# schematic_r3.net
KiCad netlist of a schematic drawn in EAGLE
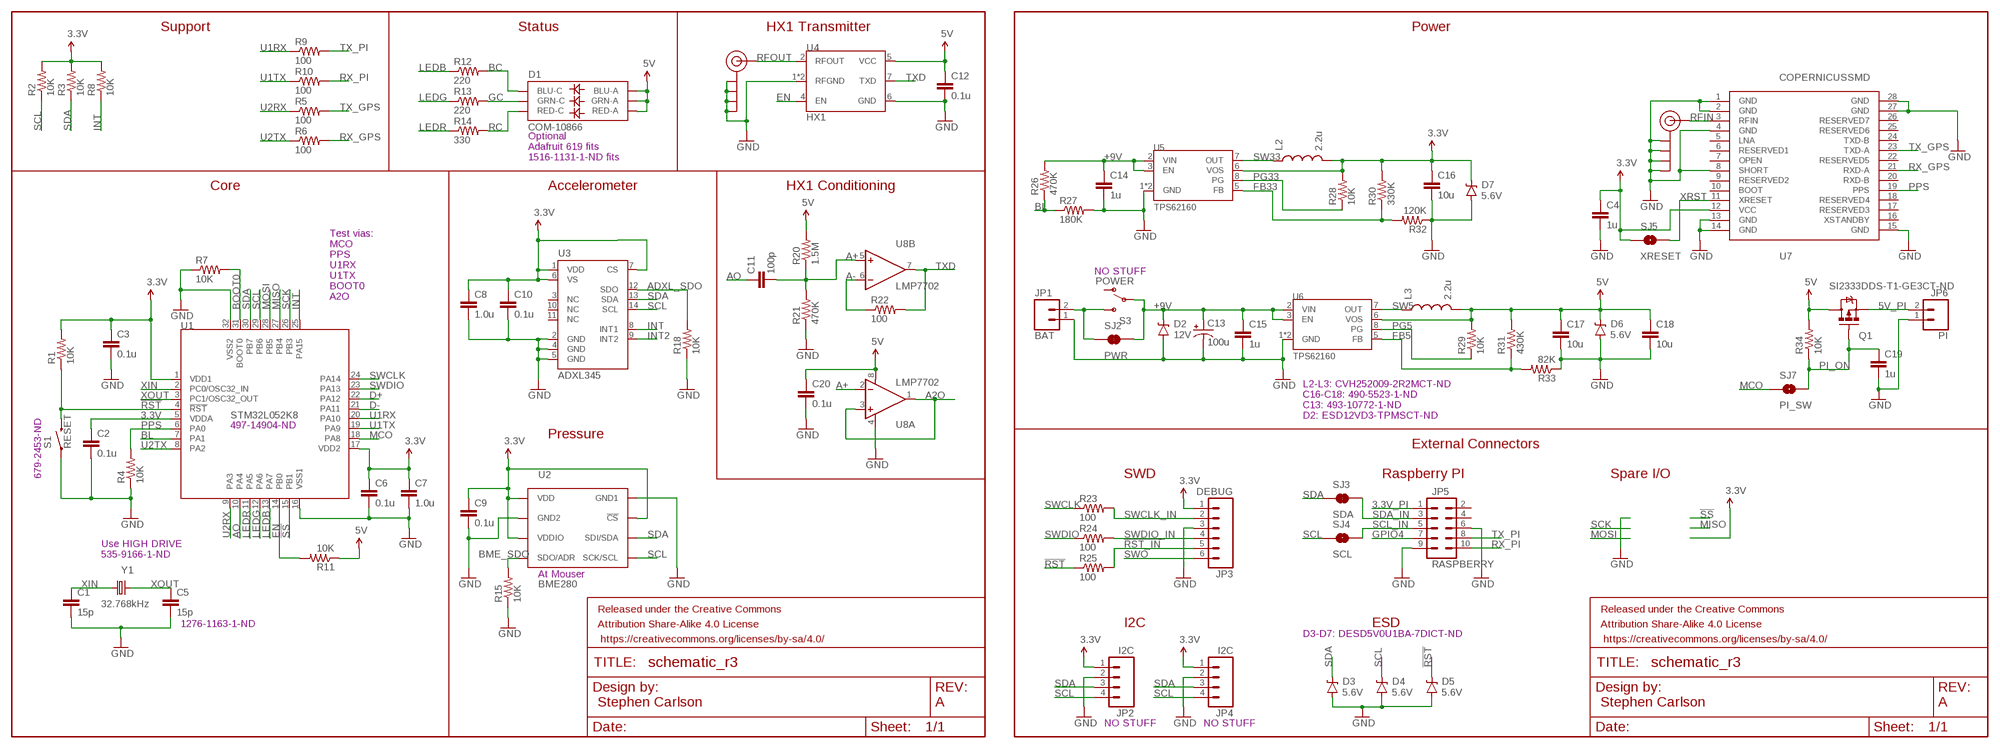
[diagram p0: schematic, sheet 1]

(export (version "E")
  (design (tool "Eeschema 10.0.6"))
  (components
    (comp (ref "C1")
      (value "15p")
      (footprint "eagle-import:0805")
      (libsource (lib "eagle-import") (part "CAP0805"))
    )
    (comp (ref "C2")
      (value "0.1u")
      (footprint "eagle-import:0805")
      (libsource (lib "eagle-import") (part "CAP0805"))
    )
    (comp (ref "C3")
      (value "0.1u")
      (footprint "eagle-import:0805")
      (libsource (lib "eagle-import") (part "CAP0805"))
    )
    (comp (ref "C4")
      (value "1u")
      (footprint "eagle-import:0805")
      (libsource (lib "eagle-import") (part "CAP0805"))
    )
    (comp (ref "C5")
      (value "15p")
      (footprint "eagle-import:0805")
      (libsource (lib "eagle-import") (part "CAP0805"))
    )
    (comp (ref "C6")
      (value "0.1u")
      (footprint "eagle-import:0805")
      (libsource (lib "eagle-import") (part "CAP0805"))
    )
    (comp (ref "C7")
      (value "1.0u")
      (footprint "eagle-import:0805")
      (libsource (lib "eagle-import") (part "CAP0805"))
    )
    (comp (ref "C8")
      (value "1.0u")
      (footprint "eagle-import:0805")
      (libsource (lib "eagle-import") (part "CAP0805"))
    )
    (comp (ref "C9")
      (value "0.1u")
      (footprint "eagle-import:0805")
      (libsource (lib "eagle-import") (part "CAP0805"))
    )
    (comp (ref "C10")
      (value "0.1u")
      (footprint "eagle-import:0805")
      (libsource (lib "eagle-import") (part "CAP0805"))
    )
    (comp (ref "C11")
      (value "100p")
      (footprint "eagle-import:0805")
      (libsource (lib "eagle-import") (part "CAP0805"))
    )
    (comp (ref "C12")
      (value "0.1u")
      (footprint "eagle-import:0805")
      (libsource (lib "eagle-import") (part "CAP0805"))
    )
    (comp (ref "C13")
      (value "100u")
      (footprint "eagle-import:CPOL-RADIAL-10UF-25V")
      (libsource (lib "eagle-import") (part "CAP_POLPTH2"))
    )
    (comp (ref "C14")
      (value "1u")
      (footprint "eagle-import:0805")
      (libsource (lib "eagle-import") (part "CAP0805"))
    )
    (comp (ref "C15")
      (value "1u")
      (footprint "eagle-import:0805")
      (libsource (lib "eagle-import") (part "CAP0805"))
    )
    (comp (ref "C16")
      (value "10u")
      (footprint "eagle-import:0805")
      (libsource (lib "eagle-import") (part "CAP0805"))
    )
    (comp (ref "C17")
      (value "10u")
      (footprint "eagle-import:0805")
      (libsource (lib "eagle-import") (part "CAP0805"))
    )
    (comp (ref "C18")
      (value "10u")
      (footprint "eagle-import:0805")
      (libsource (lib "eagle-import") (part "CAP0805"))
    )
    (comp (ref "C19")
      (value "1u")
      (footprint "eagle-import:0805")
      (libsource (lib "eagle-import") (part "CAP0805"))
    )
    (comp (ref "C20")
      (value "0.1u")
      (footprint "eagle-import:0805")
      (libsource (lib "eagle-import") (part "CAP0805"))
    )
    (comp (ref "D1")
      (value "COM-10866")
      (footprint "eagle-import:LED-TRICOLOR-5050")
      (libsource (lib "eagle-import") (part "LED-TRICOLOR-5050NO_IC"))
    )
    (comp (ref "D2")
      (value "12V")
      (footprint "eagle-import:SOD-323")
      (libsource (lib "eagle-import") (part "DIODE-ZENER5.6V"))
    )
    (comp (ref "D3")
      (value "5.6V")
      (footprint "eagle-import:SOD-323")
      (libsource (lib "eagle-import") (part "DIODE-ZENER5.6V"))
    )
    (comp (ref "D4")
      (value "5.6V")
      (footprint "eagle-import:SOD-323")
      (libsource (lib "eagle-import") (part "DIODE-ZENER5.6V"))
    )
    (comp (ref "D5")
      (value "5.6V")
      (footprint "eagle-import:SOD-323")
      (libsource (lib "eagle-import") (part "DIODE-ZENER5.6V"))
    )
    (comp (ref "D6")
      (value "5.6V")
      (footprint "eagle-import:SOD-323")
      (libsource (lib "eagle-import") (part "DIODE-ZENER5.6V"))
    )
    (comp (ref "D7")
      (value "5.6V")
      (footprint "eagle-import:SOD-323")
      (libsource (lib "eagle-import") (part "DIODE-ZENER5.6V"))
    )
    (comp (ref "FRAME1")
      (value "FRAME-LETTERNO_PACKAGE")
      (footprint "eagle-import:DUMMY")
      (fields (field (name "DESIGNER") "Nobody"))
      (libsource (lib "eagle-import") (part "FRAME-LETTERNO_PACKAGE"))
    )
    (comp (ref "FRAME2")
      (value "FRAME-LETTERNO_PACKAGE")
      (footprint "eagle-import:DUMMY")
      (fields (field (name "DESIGNER") "Nobody"))
      (libsource (lib "eagle-import") (part "FRAME-LETTERNO_PACKAGE"))
    )
    (comp (ref "J$1")
      (value "SMA_EDGE")
      (footprint "eagle-import:SMA-EDGE")
      (libsource (lib "eagle-import") (part "SMA_EDGE"))
    )
    (comp (ref "J$2")
      (value "SMA_EDGE")
      (footprint "eagle-import:SMA-EDGE")
      (libsource (lib "eagle-import") (part "SMA_EDGE"))
    )
    (comp (ref "JP1")
      (value "BAT")
      (footprint "eagle-import:1X02")
      (libsource (lib "eagle-import") (part "M02PTH"))
    )
    (comp (ref "JP2")
      (value "I2C")
      (footprint "eagle-import:1X04_LOCK")
      (libsource (lib "eagle-import") (part "M04LOCK"))
    )
    (comp (ref "JP3")
      (value "DEBUG")
      (footprint "eagle-import:1X06_LOCK")
      (libsource (lib "eagle-import") (part "M06LOCK"))
    )
    (comp (ref "JP4")
      (value "I2C")
      (footprint "eagle-import:1X04_LOCK")
      (libsource (lib "eagle-import") (part "M04LOCK"))
    )
    (comp (ref "JP5")
      (value "RASPBERRY")
      (footprint "eagle-import:AVR_ICSP")
      (libsource (lib "eagle-import") (part "M05X2PTH"))
    )
    (comp (ref "JP6")
      (value "PI")
      (footprint "eagle-import:1X02")
      (libsource (lib "eagle-import") (part "M02PTH"))
    )
    (comp (ref "L2")
      (value "2.2u")
      (footprint "eagle-import:1008")
      (libsource (lib "eagle-import") (part "INDUCTOR1008"))
    )
    (comp (ref "L3")
      (value "2.2u")
      (footprint "eagle-import:1008")
      (libsource (lib "eagle-import") (part "INDUCTOR1008"))
    )
    (comp (ref "Q1")
      (value "SI2333DDS-T1-GE3CT-ND")
      (footprint "eagle-import:SOT23-3")
      (libsource (lib "eagle-import") (part "MOSFET-PCHANNELSMD"))
    )
    (comp (ref "R1")
      (value "10K")
      (footprint "eagle-import:0805")
      (libsource (lib "eagle-import") (part "RESISTOR0805-RES"))
    )
    (comp (ref "R2")
      (value "10K")
      (footprint "eagle-import:0805")
      (libsource (lib "eagle-import") (part "RESISTOR0805-RES"))
    )
    (comp (ref "R3")
      (value "10K")
      (footprint "eagle-import:0805")
      (libsource (lib "eagle-import") (part "RESISTOR0805-RES"))
    )
    (comp (ref "R4")
      (value "10K")
      (footprint "eagle-import:0805")
      (libsource (lib "eagle-import") (part "RESISTOR0805-RES"))
    )
    (comp (ref "R5")
      (value "100")
      (footprint "eagle-import:0805")
      (libsource (lib "eagle-import") (part "RESISTOR0805-RES"))
    )
    (comp (ref "R6")
      (value "100")
      (footprint "eagle-import:0805")
      (libsource (lib "eagle-import") (part "RESISTOR0805-RES"))
    )
    (comp (ref "R7")
      (value "10K")
      (footprint "eagle-import:0805")
      (libsource (lib "eagle-import") (part "RESISTOR0805-RES"))
    )
    (comp (ref "R8")
      (value "10K")
      (footprint "eagle-import:0805")
      (libsource (lib "eagle-import") (part "RESISTOR0805-RES"))
    )
    (comp (ref "R9")
      (value "100")
      (footprint "eagle-import:0805")
      (libsource (lib "eagle-import") (part "RESISTOR0805-RES"))
    )
    (comp (ref "R10")
      (value "100")
      (footprint "eagle-import:0805")
      (libsource (lib "eagle-import") (part "RESISTOR0805-RES"))
    )
    (comp (ref "R11")
      (value "10K")
      (footprint "eagle-import:0805")
      (libsource (lib "eagle-import") (part "RESISTOR0805-RES"))
    )
    (comp (ref "R12")
      (value "220")
      (footprint "eagle-import:0805")
      (libsource (lib "eagle-import") (part "RESISTOR0805-RES"))
    )
    (comp (ref "R13")
      (value "220")
      (footprint "eagle-import:0805")
      (libsource (lib "eagle-import") (part "RESISTOR0805-RES"))
    )
    (comp (ref "R14")
      (value "330")
      (footprint "eagle-import:0805")
      (libsource (lib "eagle-import") (part "RESISTOR0805-RES"))
    )
    (comp (ref "R15")
      (value "10K")
      (footprint "eagle-import:0805")
      (libsource (lib "eagle-import") (part "RESISTOR0805-RES"))
    )
    (comp (ref "R18")
      (value "10K")
      (footprint "eagle-import:0805")
      (libsource (lib "eagle-import") (part "RESISTOR0805-RES"))
    )
    (comp (ref "R20")
      (value "1.5M")
      (footprint "eagle-import:0805")
      (libsource (lib "eagle-import") (part "RESISTOR0805-RES"))
    )
    (comp (ref "R21")
      (value "470K")
      (footprint "eagle-import:0805")
      (libsource (lib "eagle-import") (part "RESISTOR0805-RES"))
    )
    (comp (ref "R22")
      (value "100")
      (footprint "eagle-import:0805")
      (libsource (lib "eagle-import") (part "RESISTOR0805-RES"))
    )
    (comp (ref "R23")
      (value "100")
      (footprint "eagle-import:0805")
      (libsource (lib "eagle-import") (part "RESISTOR0805-RES"))
    )
    (comp (ref "R24")
      (value "100")
      (footprint "eagle-import:0805")
      (libsource (lib "eagle-import") (part "RESISTOR0805-RES"))
    )
    (comp (ref "R25")
      (value "100")
      (footprint "eagle-import:0805")
      (libsource (lib "eagle-import") (part "RESISTOR0805-RES"))
    )
    (comp (ref "R26")
      (value "470K")
      (footprint "eagle-import:0805")
      (libsource (lib "eagle-import") (part "RESISTOR0805-RES"))
    )
    (comp (ref "R27")
      (value "180K")
      (footprint "eagle-import:0805")
      (libsource (lib "eagle-import") (part "RESISTOR0805-RES"))
    )
    (comp (ref "R28")
      (value "10K")
      (footprint "eagle-import:0805")
      (libsource (lib "eagle-import") (part "RESISTOR0805-RES"))
    )
    (comp (ref "R29")
      (value "10K")
      (footprint "eagle-import:0805")
      (libsource (lib "eagle-import") (part "RESISTOR0805-RES"))
    )
    (comp (ref "R30")
      (value "330K")
      (footprint "eagle-import:0805")
      (libsource (lib "eagle-import") (part "RESISTOR0805-RES"))
    )
    (comp (ref "R31")
      (value "430K")
      (footprint "eagle-import:0805")
      (libsource (lib "eagle-import") (part "RESISTOR0805-RES"))
    )
    (comp (ref "R32")
      (value "120K")
      (footprint "eagle-import:0805")
      (libsource (lib "eagle-import") (part "RESISTOR0805-RES"))
    )
    (comp (ref "R33")
      (value "82K")
      (footprint "eagle-import:0805")
      (libsource (lib "eagle-import") (part "RESISTOR0805-RES"))
    )
    (comp (ref "R34")
      (value "10K")
      (footprint "eagle-import:0805")
      (libsource (lib "eagle-import") (part "RESISTOR0805-RES"))
    )
    (comp (ref "S1")
      (value "RESET")
      (footprint "eagle-import:TACTILE-PTH-THIN")
      (libsource (lib "eagle-import") (part "SWITCH"))
    )
    (comp (ref "S3")
      (value "POWER")
      (footprint "eagle-import:SWITCH-SPDT")
      (libsource (lib "eagle-import") (part "SWITCH-SPDTPTH"))
    )
    (comp (ref "SJ2")
      (value "PWR")
      (footprint "eagle-import:PAD-JUMPER-2-NC_BY_TRACE_YES_SILK")
      (libsource (lib "eagle-import") (part "JUMPER-PAD-2-NC_BY_TRACE"))
    )
    (comp (ref "SJ3")
      (value "SDA")
      (footprint "eagle-import:PAD-JUMPER-2-NC_BY_TRACE_YES_SILK")
      (libsource (lib "eagle-import") (part "JUMPER-PAD-2-NC_BY_TRACE"))
    )
    (comp (ref "SJ4")
      (value "SCL")
      (footprint "eagle-import:PAD-JUMPER-2-NC_BY_TRACE_YES_SILK")
      (libsource (lib "eagle-import") (part "JUMPER-PAD-2-NC_BY_TRACE"))
    )
    (comp (ref "SJ5")
      (value "XRESET")
      (footprint "eagle-import:PAD-JUMPER-2-NO_YES_SILK")
      (libsource (lib "eagle-import") (part "JUMPER-PAD-2-NOYES_SILK"))
    )
    (comp (ref "SJ7")
      (value "PI_SW")
      (footprint "eagle-import:PAD-JUMPER-2-NO_YES_SILK")
      (libsource (lib "eagle-import") (part "JUMPER-PAD-2-NOYES_SILK"))
    )
    (comp (ref "U1")
      (value "STM32L052K8")
      (footprint "eagle-import:TQFP32-08")
      (libsource (lib "eagle-import") (part "STM32L05K"))
    )
    (comp (ref "U2")
      (value "BME280")
      (footprint "eagle-import:BME280_LGA")
      (libsource (lib "eagle-import") (part "BME280"))
    )
    (comp (ref "U3")
      (value "ADXL345")
      (footprint "eagle-import:LGA14")
      (libsource (lib "eagle-import") (part "ADXL345"))
    )
    (comp (ref "U4")
      (value "HX1")
      (footprint "eagle-import:1X12")
      (libsource (lib "eagle-import") (part "HX1"))
    )
    (comp (ref "U5")
      (value "TPS62160")
      (footprint "eagle-import:MSOP8")
      (libsource (lib "eagle-import") (part "TPS62160"))
    )
    (comp (ref "U6")
      (value "TPS62160")
      (footprint "eagle-import:MSOP8")
      (libsource (lib "eagle-import") (part "TPS62160"))
    )
    (comp (ref "U7")
      (value "COPERNICUSSMD")
      (footprint "eagle-import:COPERNICUS")
      (libsource (lib "eagle-import") (part "COPERNICUSSMD"))
    )
    (comp (ref "U8")
      (value "LMP7702")
      (footprint "eagle-import:SO08")
      (libsource (lib "eagle-import") (part "OPAMP-DUALU"))
    )
    (comp (ref "Y1")
      (value "32.768kHz")
      (footprint "eagle-import:ABS25")
      (libsource (lib "eagle-import") (part "CRYSTAL"))
    )
  )
  (nets
    (net (code "1") (name "/+9V") (class "Default")
      (node (ref "C13") (pin "1") (pinfunction "+_1") (pintype "passive"))
      (node (ref "C14") (pin "1") (pinfunction "1_1") (pintype "passive"))
      (node (ref "C15") (pin "1") (pinfunction "1_1") (pintype "passive"))
      (node (ref "D2") (pin "C") (pinfunction "C_C") (pintype "passive"))
      (node (ref "R26") (pin "2") (pinfunction "2_2") (pintype "passive"))
      (node (ref "S3") (pin "2") (pinfunction "P_2") (pintype "passive"))
      (node (ref "SJ2") (pin "2") (pinfunction "2_2") (pintype "passive"))
      (node (ref "U5") (pin "2") (pinfunction "VIN_2") (pintype "power_in"))
      (node (ref "U5") (pin "3") (pinfunction "EN_3") (pintype "input"))
      (node (ref "U6") (pin "2") (pinfunction "VIN_2") (pintype "power_in"))
      (node (ref "U6") (pin "3") (pinfunction "EN_3") (pintype "input"))
    )
    (net (code "2") (name "/3.3V_PI") (class "Default")
      (node (ref "JP5") (pin "1") (pinfunction "1_1") (pintype "passive"))
    )
    (net (code "3") (name "/5V_PI") (class "Default")
      (node (ref "JP6") (pin "2") (pinfunction "2_2") (pintype "passive"))
      (node (ref "Q1") (pin "2") (pinfunction "S_2") (pintype "passive"))
    )
    (net (code "4") (name "/A+") (class "Default")
      (node (ref "C11") (pin "2") (pinfunction "2_2") (pintype "passive"))
      (node (ref "R20") (pin "1") (pinfunction "1_1") (pintype "passive"))
      (node (ref "R21") (pin "2") (pinfunction "2_2") (pintype "passive"))
      (node (ref "U8") (pin "2") (pinfunction "-IN_2") (pintype "input"))
      (node (ref "U8") (pin "5") (pinfunction "+IN_5") (pintype "input"))
    )
    (net (code "5") (name "/A-") (class "Default")
      (node (ref "R22") (pin "1") (pinfunction "1_1") (pintype "passive"))
      (node (ref "U8") (pin "6") (pinfunction "-IN_6") (pintype "input"))
    )
    (net (code "6") (name "/A2O") (class "Default")
      (node (ref "U8") (pin "1") (pinfunction "OUT_1") (pintype "output"))
      (node (ref "U8") (pin "3") (pinfunction "+IN_3") (pintype "input"))
    )
    (net (code "7") (name "/ADXL_SDO") (class "Default")
      (node (ref "R18") (pin "2") (pinfunction "2_2") (pintype "passive"))
      (node (ref "U3") (pin "12") (pinfunction "SDO_12") (pintype "bidirectional"))
    )
    (net (code "8") (name "/AO") (class "Default")
      (node (ref "C11") (pin "1") (pinfunction "1_1") (pintype "passive"))
      (node (ref "U1") (pin "10") (pinfunction "PA4_10") (pintype "bidirectional"))
    )
    (net (code "9") (name "/BC") (class "Default")
      (node (ref "D1") (pin "4") (pinfunction "BLU-C_4") (pintype "bidirectional"))
      (node (ref "R12") (pin "2") (pinfunction "2_2") (pintype "passive"))
    )
    (net (code "10") (name "/BL") (class "Default")
      (node (ref "R26") (pin "1") (pinfunction "1_1") (pintype "passive"))
      (node (ref "R27") (pin "1") (pinfunction "1_1") (pintype "passive"))
      (node (ref "U1") (pin "7") (pinfunction "PA1_7") (pintype "bidirectional"))
    )
    (net (code "11") (name "/BME_SDO") (class "Default")
      (node (ref "R15") (pin "2") (pinfunction "2_2") (pintype "passive"))
      (node (ref "U2") (pin "P$5") (pinfunction "SDO/ADR_P$5") (pintype "bidirectional"))
    )
    (net (code "12") (name "/BOOT0") (class "Default")
      (node (ref "R7") (pin "2") (pinfunction "2_2") (pintype "passive"))
      (node (ref "U1") (pin "31") (pinfunction "BOOT0_31") (pintype "input"))
    )
    (net (code "13") (name "/D+") (class "Default")
      (node (ref "U1") (pin "22") (pinfunction "PA12_22") (pintype "bidirectional"))
    )
    (net (code "14") (name "/D-") (class "Default")
      (node (ref "U1") (pin "21") (pinfunction "PA11_21") (pintype "bidirectional"))
    )
    (net (code "15") (name "/EN") (class "Default")
      (node (ref "R11") (pin "2") (pinfunction "2_2") (pintype "passive"))
      (node (ref "U1") (pin "14") (pinfunction "PB0_14") (pintype "bidirectional"))
      (node (ref "U4") (pin "4") (pinfunction "EN_4") (pintype "input"))
    )
    (net (code "16") (name "/FB5") (class "Default")
      (node (ref "R31") (pin "1") (pinfunction "1_1") (pintype "passive"))
      (node (ref "R33") (pin "2") (pinfunction "2_2") (pintype "passive"))
      (node (ref "U6") (pin "5") (pinfunction "FB_5") (pintype "input"))
    )
    (net (code "17") (name "/FB33") (class "Default")
      (node (ref "R30") (pin "1") (pinfunction "1_1") (pintype "passive"))
      (node (ref "R32") (pin "2") (pinfunction "2_2") (pintype "passive"))
      (node (ref "U5") (pin "5") (pinfunction "FB_5") (pintype "input"))
    )
    (net (code "18") (name "/GC") (class "Default")
      (node (ref "D1") (pin "6") (pinfunction "GRN-C_6") (pintype "bidirectional"))
      (node (ref "R13") (pin "2") (pinfunction "2_2") (pintype "passive"))
    )
    (net (code "19") (name "/GPIO4") (class "Default")
      (node (ref "JP5") (pin "7") (pinfunction "7_7") (pintype "passive"))
    )
    (net (code "20") (name "/INT") (class "Default")
      (node (ref "R8") (pin "1") (pinfunction "1_1") (pintype "passive"))
      (node (ref "U1") (pin "25") (pinfunction "PA15_25") (pintype "bidirectional"))
      (node (ref "U3") (pin "8") (pinfunction "INT1_8") (pintype "bidirectional"))
    )
    (net (code "21") (name "/INT2") (class "Default")
      (node (ref "U3") (pin "9") (pinfunction "INT2_9") (pintype "bidirectional"))
    )
    (net (code "22") (name "/LEDB") (class "Default")
      (node (ref "R12") (pin "1") (pinfunction "1_1") (pintype "passive"))
      (node (ref "U1") (pin "13") (pinfunction "PA7_13") (pintype "bidirectional"))
    )
    (net (code "23") (name "/LEDG") (class "Default")
      (node (ref "R13") (pin "1") (pinfunction "1_1") (pintype "passive"))
      (node (ref "U1") (pin "12") (pinfunction "PA6_12") (pintype "bidirectional"))
    )
    (net (code "24") (name "/LEDR") (class "Default")
      (node (ref "R14") (pin "1") (pinfunction "1_1") (pintype "passive"))
      (node (ref "U1") (pin "11") (pinfunction "PA5_11") (pintype "bidirectional"))
    )
    (net (code "25") (name "/MCO") (class "Default")
      (node (ref "SJ7") (pin "1") (pinfunction "1_1") (pintype "passive"))
      (node (ref "U1") (pin "18") (pinfunction "PA8_18") (pintype "bidirectional"))
    )
    (net (code "26") (name "/MISO") (class "Default")
      (node (ref "U1") (pin "27") (pinfunction "PB4_27") (pintype "bidirectional"))
    )
    (net (code "27") (name "/MOSI") (class "Default")
      (node (ref "U1") (pin "28") (pinfunction "PB5_28") (pintype "bidirectional"))
    )
    (net (code "28") (name "/PG5") (class "Default")
      (node (ref "R29") (pin "1") (pinfunction "1_1") (pintype "passive"))
      (node (ref "U6") (pin "8") (pinfunction "PG_8") (pintype "open_collector"))
    )
    (net (code "29") (name "/PG33") (class "Default")
      (node (ref "R28") (pin "1") (pinfunction "1_1") (pintype "passive"))
      (node (ref "U5") (pin "8") (pinfunction "PG_8") (pintype "open_collector"))
    )
    (net (code "30") (name "/PI_ON") (class "Default")
      (node (ref "C19") (pin "1") (pinfunction "1_1") (pintype "passive"))
      (node (ref "Q1") (pin "1") (pinfunction "G_1") (pintype "passive"))
      (node (ref "R34") (pin "1") (pinfunction "1_1") (pintype "passive"))
      (node (ref "SJ7") (pin "2") (pinfunction "2_2") (pintype "passive"))
    )
    (net (code "31") (name "/PPS") (class "Default")
      (node (ref "R4") (pin "2") (pinfunction "2_2") (pintype "passive"))
      (node (ref "U1") (pin "6") (pinfunction "PA0_6") (pintype "bidirectional"))
      (node (ref "U7") (pin "19") (pinfunction "PPS_19") (pintype "bidirectional"))
    )
    (net (code "32") (name "/RC") (class "Default")
      (node (ref "D1") (pin "5") (pinfunction "RED-C_5") (pintype "bidirectional"))
      (node (ref "R14") (pin "2") (pinfunction "2_2") (pintype "passive"))
    )
    (net (code "33") (name "/RFIN") (class "Default")
      (node (ref "J$2") (pin "SIG") (pinfunction "SIGNAL_SIG") (pintype "bidirectional"))
      (node (ref "U7") (pin "3") (pinfunction "RFIN_3") (pintype "bidirectional"))
    )
    (net (code "34") (name "/RFOUT") (class "Default")
      (node (ref "J$1") (pin "SIG") (pinfunction "SIGNAL_SIG") (pintype "bidirectional"))
      (node (ref "U4") (pin "2") (pinfunction "RFOUT_2") (pintype "output"))
    )
    (net (code "35") (name "/RX_GPS") (class "Default")
      (node (ref "R6") (pin "2") (pinfunction "2_2") (pintype "passive"))
      (node (ref "U7") (pin "21") (pinfunction "RXD-A_21") (pintype "bidirectional"))
    )
    (net (code "36") (name "/RX_PI") (class "Default")
      (node (ref "JP5") (pin "10") (pinfunction "10_10") (pintype "passive"))
      (node (ref "R10") (pin "2") (pinfunction "2_2") (pintype "passive"))
    )
    (net (code "37") (name "/SCK") (class "Default")
      (node (ref "U1") (pin "26") (pinfunction "PB3_26") (pintype "bidirectional"))
    )
    (net (code "38") (name "/SCL") (class "Default")
      (node (ref "D4") (pin "C") (pinfunction "C_C") (pintype "passive"))
      (node (ref "JP2") (pin "4") (pinfunction "4_4") (pintype "passive"))
      (node (ref "JP4") (pin "4") (pinfunction "4_4") (pintype "passive"))
      (node (ref "R2") (pin "1") (pinfunction "1_1") (pintype "passive"))
      (node (ref "SJ4") (pin "1") (pinfunction "1_1") (pintype "passive"))
      (node (ref "U1") (pin "29") (pinfunction "PB6_29") (pintype "bidirectional"))
      (node (ref "U2") (pin "P$4") (pinfunction "SCK/SCL_P$4") (pintype "bidirectional"))
      (node (ref "U3") (pin "14") (pinfunction "SCL_14") (pintype "bidirectional"))
    )
    (net (code "39") (name "/SCL_IN") (class "Default")
      (node (ref "JP5") (pin "5") (pinfunction "5_5") (pintype "passive"))
      (node (ref "SJ4") (pin "2") (pinfunction "2_2") (pintype "passive"))
    )
    (net (code "40") (name "/SDA") (class "Default")
      (node (ref "D3") (pin "C") (pinfunction "C_C") (pintype "passive"))
      (node (ref "JP2") (pin "3") (pinfunction "3_3") (pintype "passive"))
      (node (ref "JP4") (pin "3") (pinfunction "3_3") (pintype "passive"))
      (node (ref "R3") (pin "1") (pinfunction "1_1") (pintype "passive"))
      (node (ref "SJ3") (pin "1") (pinfunction "1_1") (pintype "passive"))
      (node (ref "U1") (pin "30") (pinfunction "PB7_30") (pintype "bidirectional"))
      (node (ref "U2") (pin "P$3") (pinfunction "SDI/SDA_P$3") (pintype "bidirectional"))
      (node (ref "U3") (pin "13") (pinfunction "SDA_13") (pintype "bidirectional"))
    )
    (net (code "41") (name "/SDA_IN") (class "Default")
      (node (ref "JP5") (pin "3") (pinfunction "3_3") (pintype "passive"))
      (node (ref "SJ3") (pin "2") (pinfunction "2_2") (pintype "passive"))
    )
    (net (code "42") (name "/SW5") (class "Default")
      (node (ref "L3") (pin "1") (pinfunction "1_1") (pintype "passive"))
      (node (ref "U6") (pin "7") (pinfunction "OUT_7") (pintype "output"))
    )
    (net (code "43") (name "/SW33") (class "Default")
      (node (ref "L2") (pin "1") (pinfunction "1_1") (pintype "passive"))
      (node (ref "U5") (pin "7") (pinfunction "OUT_7") (pintype "output"))
    )
    (net (code "44") (name "/SWCLK") (class "Default")
      (node (ref "R23") (pin "1") (pinfunction "1_1") (pintype "passive"))
      (node (ref "U1") (pin "24") (pinfunction "PA14_24") (pintype "bidirectional"))
    )
    (net (code "45") (name "/SWCLK_IN") (class "Default")
      (node (ref "JP3") (pin "2") (pinfunction "2_2") (pintype "passive"))
      (node (ref "R23") (pin "2") (pinfunction "2_2") (pintype "passive"))
    )
    (net (code "46") (name "/SWDIO") (class "Default")
      (node (ref "R24") (pin "1") (pinfunction "1_1") (pintype "passive"))
      (node (ref "U1") (pin "23") (pinfunction "PA13_23") (pintype "bidirectional"))
    )
    (net (code "47") (name "/SWDIO_IN") (class "Default")
      (node (ref "JP3") (pin "4") (pinfunction "4_4") (pintype "passive"))
      (node (ref "R24") (pin "2") (pinfunction "2_2") (pintype "passive"))
    )
    (net (code "48") (name "/SWO") (class "Default")
      (node (ref "JP3") (pin "6") (pinfunction "6_6") (pintype "passive"))
    )
    (net (code "49") (name "/TXD") (class "Default")
      (node (ref "R22") (pin "2") (pinfunction "2_2") (pintype "passive"))
      (node (ref "U4") (pin "7") (pinfunction "TXD_7") (pintype "input"))
      (node (ref "U8") (pin "7") (pinfunction "OUT_7") (pintype "output"))
    )
    (net (code "50") (name "/TX_GPS") (class "Default")
      (node (ref "R5") (pin "2") (pinfunction "2_2") (pintype "passive"))
      (node (ref "U7") (pin "23") (pinfunction "TXD-A_23") (pintype "bidirectional"))
    )
    (net (code "51") (name "/TX_PI") (class "Default")
      (node (ref "JP5") (pin "8") (pinfunction "8_8") (pintype "passive"))
      (node (ref "R9") (pin "2") (pinfunction "2_2") (pintype "passive"))
    )
    (net (code "52") (name "/U1RX") (class "Default")
      (node (ref "R9") (pin "1") (pinfunction "1_1") (pintype "passive"))
      (node (ref "U1") (pin "20") (pinfunction "PA10_20") (pintype "bidirectional"))
    )
    (net (code "53") (name "/U1TX") (class "Default")
      (node (ref "R10") (pin "1") (pinfunction "1_1") (pintype "passive"))
      (node (ref "U1") (pin "19") (pinfunction "PA9_19") (pintype "bidirectional"))
    )
    (net (code "54") (name "/U2RX") (class "Default")
      (node (ref "R5") (pin "1") (pinfunction "1_1") (pintype "passive"))
      (node (ref "U1") (pin "9") (pinfunction "PA3_9") (pintype "bidirectional"))
    )
    (net (code "55") (name "/U2TX") (class "Default")
      (node (ref "R6") (pin "1") (pinfunction "1_1") (pintype "passive"))
      (node (ref "U1") (pin "8") (pinfunction "PA2_8") (pintype "bidirectional"))
    )
    (net (code "56") (name "/XIN") (class "Default")
      (node (ref "C1") (pin "1") (pinfunction "1_1") (pintype "passive"))
      (node (ref "U1") (pin "2") (pinfunction "PC0/OSC32_IN_2") (pintype "bidirectional"))
      (node (ref "Y1") (pin "1") (pinfunction "1_1") (pintype "passive"))
    )
    (net (code "57") (name "/XOUT") (class "Default")
      (node (ref "C5") (pin "1") (pinfunction "1_1") (pintype "passive"))
      (node (ref "U1") (pin "3") (pinfunction "PC1/OSC32_OUT_3") (pintype "bidirectional"))
      (node (ref "Y1") (pin "4") (pinfunction "2_4") (pintype "passive"))
    )
    (net (code "58") (name "/XRST") (class "Default")
      (node (ref "SJ5") (pin "2") (pinfunction "2_2") (pintype "passive"))
      (node (ref "U7") (pin "11") (pinfunction "XRESET_11") (pintype "bidirectional"))
    )
    (net (code "59") (name "/~{RST_IN}") (class "Default")
      (node (ref "JP3") (pin "5") (pinfunction "5_5") (pintype "passive"))
      (node (ref "R25") (pin "2") (pinfunction "2_2") (pintype "passive"))
    )
    (net (code "60") (name "/~{RST}") (class "Default")
      (node (ref "D5") (pin "C") (pinfunction "C_C") (pintype "passive"))
      (node (ref "R1") (pin "1") (pinfunction "1_1") (pintype "passive"))
      (node (ref "R25") (pin "1") (pinfunction "1_1") (pintype "passive"))
      (node (ref "S1") (pin "2") (pinfunction "2_2") (pintype "passive"))
      (node (ref "U1") (pin "4") (pinfunction "~{RST}_4") (pintype "input"))
    )
    (net (code "61") (name "/~{SS}") (class "Default")
      (node (ref "U1") (pin "15") (pinfunction "PB1_15") (pintype "bidirectional"))
    )
    (net (code "62") (name "3.3V") (class "Default")
      (node (ref "C10") (pin "1") (pinfunction "1_1") (pintype "passive"))
      (node (ref "C16") (pin "1") (pinfunction "1_1") (pintype "passive"))
      (node (ref "C2") (pin "1") (pinfunction "1_1") (pintype "passive"))
      (node (ref "C3") (pin "1") (pinfunction "1_1") (pintype "passive"))
      (node (ref "C4") (pin "1") (pinfunction "1_1") (pintype "passive"))
      (node (ref "C6") (pin "1") (pinfunction "1_1") (pintype "passive"))
      (node (ref "C7") (pin "1") (pinfunction "1_1") (pintype "passive"))
      (node (ref "C8") (pin "1") (pinfunction "1_1") (pintype "passive"))
      (node (ref "C9") (pin "1") (pinfunction "1_1") (pintype "passive"))
      (node (ref "D7") (pin "C") (pinfunction "C_C") (pintype "passive"))
      (node (ref "JP2") (pin "1") (pinfunction "1_1") (pintype "passive"))
      (node (ref "JP3") (pin "1") (pinfunction "1_1") (pintype "passive"))
      (node (ref "JP4") (pin "1") (pinfunction "1_1") (pintype "passive"))
      (node (ref "L2") (pin "2") (pinfunction "2_2") (pintype "passive"))
      (node (ref "R1") (pin "2") (pinfunction "2_2") (pintype "passive"))
      (node (ref "R2") (pin "2") (pinfunction "2_2") (pintype "passive"))
      (node (ref "R28") (pin "2") (pinfunction "2_2") (pintype "passive"))
      (node (ref "R3") (pin "2") (pinfunction "2_2") (pintype "passive"))
      (node (ref "R30") (pin "2") (pinfunction "2_2") (pintype "passive"))
      (node (ref "R8") (pin "2") (pinfunction "2_2") (pintype "passive"))
      (node (ref "SJ5") (pin "1") (pinfunction "1_1") (pintype "passive"))
      (node (ref "U1") (pin "1") (pinfunction "VDD1_1") (pintype "power_in"))
      (node (ref "U1") (pin "17") (pinfunction "VDD2_17") (pintype "power_in"))
      (node (ref "U1") (pin "5") (pinfunction "VDDA_5") (pintype "power_in"))
      (node (ref "U2") (pin "P$2") (pinfunction "~{CS}_P$2") (pintype "bidirectional"))
      (node (ref "U2") (pin "P$6") (pinfunction "VDDIO_P$6") (pintype "bidirectional"))
      (node (ref "U2") (pin "P$8") (pinfunction "VDD_P$8") (pintype "bidirectional"))
      (node (ref "U3") (pin "1") (pinfunction "VDD_1") (pintype "bidirectional"))
      (node (ref "U3") (pin "6") (pinfunction "VS_6") (pintype "bidirectional"))
      (node (ref "U3") (pin "7") (pinfunction "CS_7") (pintype "bidirectional"))
      (node (ref "U5") (pin "6") (pinfunction "VOS_6") (pintype "input"))
      (node (ref "U7") (pin "12") (pinfunction "VCC_12") (pintype "bidirectional"))
    )
    (net (code "63") (name "5V") (class "Default")
      (node (ref "C12") (pin "1") (pinfunction "1_1") (pintype "passive"))
      (node (ref "C17") (pin "1") (pinfunction "1_1") (pintype "passive"))
      (node (ref "C18") (pin "1") (pinfunction "1_1") (pintype "passive"))
      (node (ref "C20") (pin "1") (pinfunction "1_1") (pintype "passive"))
      (node (ref "D1") (pin "1") (pinfunction "GRN-A_1") (pintype "bidirectional"))
      (node (ref "D1") (pin "2") (pinfunction "RED-A_2") (pintype "bidirectional"))
      (node (ref "D1") (pin "3") (pinfunction "BLU-A_3") (pintype "bidirectional"))
      (node (ref "D6") (pin "C") (pinfunction "C_C") (pintype "passive"))
      (node (ref "L3") (pin "2") (pinfunction "2_2") (pintype "passive"))
      (node (ref "Q1") (pin "3") (pinfunction "D_3") (pintype "passive"))
      (node (ref "R11") (pin "1") (pinfunction "1_1") (pintype "passive"))
      (node (ref "R20") (pin "2") (pinfunction "2_2") (pintype "passive"))
      (node (ref "R29") (pin "2") (pinfunction "2_2") (pintype "passive"))
      (node (ref "R31") (pin "2") (pinfunction "2_2") (pintype "passive"))
      (node (ref "R34") (pin "2") (pinfunction "2_2") (pintype "passive"))
      (node (ref "U4") (pin "5") (pinfunction "VCC_5") (pintype "power_in"))
      (node (ref "U6") (pin "6") (pinfunction "VOS_6") (pintype "input"))
      (node (ref "U8") (pin "8") (pinfunction "V+_8") (pintype "power_in"))
    )
    (net (code "64") (name "GND") (class "Default")
      (node (ref "C1") (pin "2") (pinfunction "2_2") (pintype "passive"))
      (node (ref "C10") (pin "2") (pinfunction "2_2") (pintype "passive"))
      (node (ref "C12") (pin "2") (pinfunction "2_2") (pintype "passive"))
      (node (ref "C13") (pin "2") (pinfunction "-_2") (pintype "passive"))
      (node (ref "C14") (pin "2") (pinfunction "2_2") (pintype "passive"))
      (node (ref "C15") (pin "2") (pinfunction "2_2") (pintype "passive"))
      (node (ref "C16") (pin "2") (pinfunction "2_2") (pintype "passive"))
      (node (ref "C17") (pin "2") (pinfunction "2_2") (pintype "passive"))
      (node (ref "C18") (pin "2") (pinfunction "2_2") (pintype "passive"))
      (node (ref "C19") (pin "2") (pinfunction "2_2") (pintype "passive"))
      (node (ref "C2") (pin "2") (pinfunction "2_2") (pintype "passive"))
      (node (ref "C20") (pin "2") (pinfunction "2_2") (pintype "passive"))
      (node (ref "C3") (pin "2") (pinfunction "2_2") (pintype "passive"))
      (node (ref "C4") (pin "2") (pinfunction "2_2") (pintype "passive"))
      (node (ref "C5") (pin "2") (pinfunction "2_2") (pintype "passive"))
      (node (ref "C6") (pin "2") (pinfunction "2_2") (pintype "passive"))
      (node (ref "C7") (pin "2") (pinfunction "2_2") (pintype "passive"))
      (node (ref "C8") (pin "2") (pinfunction "2_2") (pintype "passive"))
      (node (ref "C9") (pin "2") (pinfunction "2_2") (pintype "passive"))
      (node (ref "D2") (pin "A") (pinfunction "A_A") (pintype "passive"))
      (node (ref "D3") (pin "A") (pinfunction "A_A") (pintype "passive"))
      (node (ref "D4") (pin "A") (pinfunction "A_A") (pintype "passive"))
      (node (ref "D5") (pin "A") (pinfunction "A_A") (pintype "passive"))
      (node (ref "D6") (pin "A") (pinfunction "A_A") (pintype "passive"))
      (node (ref "D7") (pin "A") (pinfunction "A_A") (pintype "passive"))
      (node (ref "J$1") (pin "GND@0") (pinfunction "GND_GND@0") (pintype "bidirectional"))
      (node (ref "J$1") (pin "GND@1") (pinfunction "GND_GND@1") (pintype "bidirectional"))
      (node (ref "J$1") (pin "GND@2") (pinfunction "GND_GND@2") (pintype "bidirectional"))
      (node (ref "J$1") (pin "GND@3") (pinfunction "GND_GND@3") (pintype "bidirectional"))
      (node (ref "J$2") (pin "GND@0") (pinfunction "GND_GND@0") (pintype "bidirectional"))
      (node (ref "J$2") (pin "GND@1") (pinfunction "GND_GND@1") (pintype "bidirectional"))
      (node (ref "J$2") (pin "GND@2") (pinfunction "GND_GND@2") (pintype "bidirectional"))
      (node (ref "J$2") (pin "GND@3") (pinfunction "GND_GND@3") (pintype "bidirectional"))
      (node (ref "JP1") (pin "1") (pinfunction "1_1") (pintype "passive"))
      (node (ref "JP2") (pin "2") (pinfunction "2_2") (pintype "passive"))
      (node (ref "JP3") (pin "3") (pinfunction "3_3") (pintype "passive"))
      (node (ref "JP4") (pin "2") (pinfunction "2_2") (pintype "passive"))
      (node (ref "JP5") (pin "6") (pinfunction "6_6") (pintype "passive"))
      (node (ref "JP5") (pin "9") (pinfunction "9_9") (pintype "passive"))
      (node (ref "JP6") (pin "1") (pinfunction "1_1") (pintype "passive"))
      (node (ref "R15") (pin "1") (pinfunction "1_1") (pintype "passive"))
      (node (ref "R18") (pin "1") (pinfunction "1_1") (pintype "passive"))
      (node (ref "R21") (pin "1") (pinfunction "1_1") (pintype "passive"))
      (node (ref "R27") (pin "2") (pinfunction "2_2") (pintype "passive"))
      (node (ref "R32") (pin "1") (pinfunction "1_1") (pintype "passive"))
      (node (ref "R33") (pin "1") (pinfunction "1_1") (pintype "passive"))
      (node (ref "R4") (pin "1") (pinfunction "1_1") (pintype "passive"))
      (node (ref "R7") (pin "1") (pinfunction "1_1") (pintype "passive"))
      (node (ref "S1") (pin "1") (pinfunction "1_1") (pintype "passive"))
      (node (ref "U1") (pin "16") (pinfunction "VSS1_16") (pintype "power_in"))
      (node (ref "U1") (pin "32") (pinfunction "VSS2_32") (pintype "power_in"))
      (node (ref "U2") (pin "P$1") (pinfunction "GND1_P$1") (pintype "bidirectional"))
      (node (ref "U2") (pin "P$7") (pinfunction "GND2_P$7") (pintype "bidirectional"))
      (node (ref "U3") (pin "2") (pinfunction "GND_2") (pintype "bidirectional"))
      (node (ref "U3") (pin "4") (pinfunction "GND_4") (pintype "bidirectional"))
      (node (ref "U3") (pin "5") (pinfunction "GND_5") (pintype "bidirectional"))
      (node (ref "U4") (pin "1") (pinfunction "RFGND_1") (pintype "power_in"))
      (node (ref "U4") (pin "3") (pinfunction "RFGND_3") (pintype "power_in"))
      (node (ref "U4") (pin "6") (pinfunction "GND_6") (pintype "power_in"))
      (node (ref "U5") (pin "1") (pinfunction "GND_1") (pintype "power_in"))
      (node (ref "U5") (pin "4") (pinfunction "GND_4") (pintype "power_in"))
      (node (ref "U6") (pin "1") (pinfunction "GND_1") (pintype "power_in"))
      (node (ref "U6") (pin "4") (pinfunction "GND_4") (pintype "power_in"))
      (node (ref "U7") (pin "1") (pinfunction "GND_1") (pintype "bidirectional"))
      (node (ref "U7") (pin "13") (pinfunction "GND_13") (pintype "bidirectional"))
      (node (ref "U7") (pin "14") (pinfunction "GND_14") (pintype "bidirectional"))
      (node (ref "U7") (pin "15") (pinfunction "GND_15") (pintype "bidirectional"))
      (node (ref "U7") (pin "2") (pinfunction "GND_2") (pintype "bidirectional"))
      (node (ref "U7") (pin "27") (pinfunction "GND_27") (pintype "bidirectional"))
      (node (ref "U7") (pin "28") (pinfunction "GND_28") (pintype "bidirectional"))
      (node (ref "U7") (pin "4") (pinfunction "GND_4") (pintype "bidirectional"))
      (node (ref "U7") (pin "8") (pinfunction "SHORT_8") (pintype "bidirectional"))
      (node (ref "U8") (pin "4") (pinfunction "V-_4") (pintype "power_in"))
    )
    (net (code "65") (name "Net-(S3-S)") (class "Default")
      (node (ref "JP1") (pin "2") (pinfunction "2_2") (pintype "passive"))
      (node (ref "S3") (pin "3") (pinfunction "S_3") (pintype "passive"))
      (node (ref "SJ2") (pin "1") (pinfunction "1_1") (pintype "passive"))
    )
    (net (code "66") (name "unconnected-(JP5-Pad2)") (class "Default")
      (node (ref "JP5") (pin "2") (pinfunction "2_2") (pintype "passive"))
    )
    (net (code "67") (name "unconnected-(JP5-Pad4)") (class "Default")
      (node (ref "JP5") (pin "4") (pinfunction "4_4") (pintype "passive"))
    )
    (net (code "68") (name "unconnected-(S3-O-Pad1)") (class "Default")
      (node (ref "S3") (pin "1") (pinfunction "O_1") (pintype "passive"))
    )
    (net (code "69") (name "unconnected-(U3-NC-Pad3)") (class "Default")
      (node (ref "U3") (pin "3") (pinfunction "NC_3") (pintype "bidirectional"))
    )
    (net (code "70") (name "unconnected-(U3-NC-Pad10)") (class "Default")
      (node (ref "U3") (pin "10") (pinfunction "NC_10") (pintype "bidirectional"))
    )
    (net (code "71") (name "unconnected-(U3-NC-Pad11)") (class "Default")
      (node (ref "U3") (pin "11") (pinfunction "NC_11") (pintype "bidirectional"))
    )
    (net (code "72") (name "unconnected-(U7-BOOT-Pad10)") (class "Default")
      (node (ref "U7") (pin "10") (pinfunction "BOOT_10") (pintype "bidirectional"))
    )
    (net (code "73") (name "unconnected-(U7-LNA-Pad5)") (class "Default")
      (node (ref "U7") (pin "5") (pinfunction "LNA_5") (pintype "bidirectional"))
    )
    (net (code "74") (name "unconnected-(U7-OPEN-Pad7)") (class "Default")
      (node (ref "U7") (pin "7") (pinfunction "OPEN_7") (pintype "bidirectional"))
    )
    (net (code "75") (name "unconnected-(U7-RESERVED1-Pad6)") (class "Default")
      (node (ref "U7") (pin "6") (pinfunction "RESERVED1_6") (pintype "bidirectional"))
    )
    (net (code "76") (name "unconnected-(U7-RESERVED2-Pad9)") (class "Default")
      (node (ref "U7") (pin "9") (pinfunction "RESERVED2_9") (pintype "bidirectional"))
    )
    (net (code "77") (name "unconnected-(U7-RESERVED3-Pad17)") (class "Default")
      (node (ref "U7") (pin "17") (pinfunction "RESERVED3_17") (pintype "bidirectional"))
    )
    (net (code "78") (name "unconnected-(U7-RESERVED4-Pad18)") (class "Default")
      (node (ref "U7") (pin "18") (pinfunction "RESERVED4_18") (pintype "bidirectional"))
    )
    (net (code "79") (name "unconnected-(U7-RESERVED5-Pad22)") (class "Default")
      (node (ref "U7") (pin "22") (pinfunction "RESERVED5_22") (pintype "bidirectional"))
    )
    (net (code "80") (name "unconnected-(U7-RESERVED6-Pad25)") (class "Default")
      (node (ref "U7") (pin "25") (pinfunction "RESERVED6_25") (pintype "bidirectional"))
    )
    (net (code "81") (name "unconnected-(U7-RESERVED7-Pad26)") (class "Default")
      (node (ref "U7") (pin "26") (pinfunction "RESERVED7_26") (pintype "bidirectional"))
    )
    (net (code "82") (name "unconnected-(U7-RXD-B-Pad20)") (class "Default")
      (node (ref "U7") (pin "20") (pinfunction "RXD-B_20") (pintype "bidirectional"))
    )
    (net (code "83") (name "unconnected-(U7-TXD-B-Pad24)") (class "Default")
      (node (ref "U7") (pin "24") (pinfunction "TXD-B_24") (pintype "bidirectional"))
    )
    (net (code "84") (name "unconnected-(U7-XSTANDBY-Pad16)") (class "Default")
      (node (ref "U7") (pin "16") (pinfunction "XSTANDBY_16") (pintype "bidirectional"))
    )
  )
)
